# Sheet1.net
KiCad netlist of a schematic drawn in Altium Designer
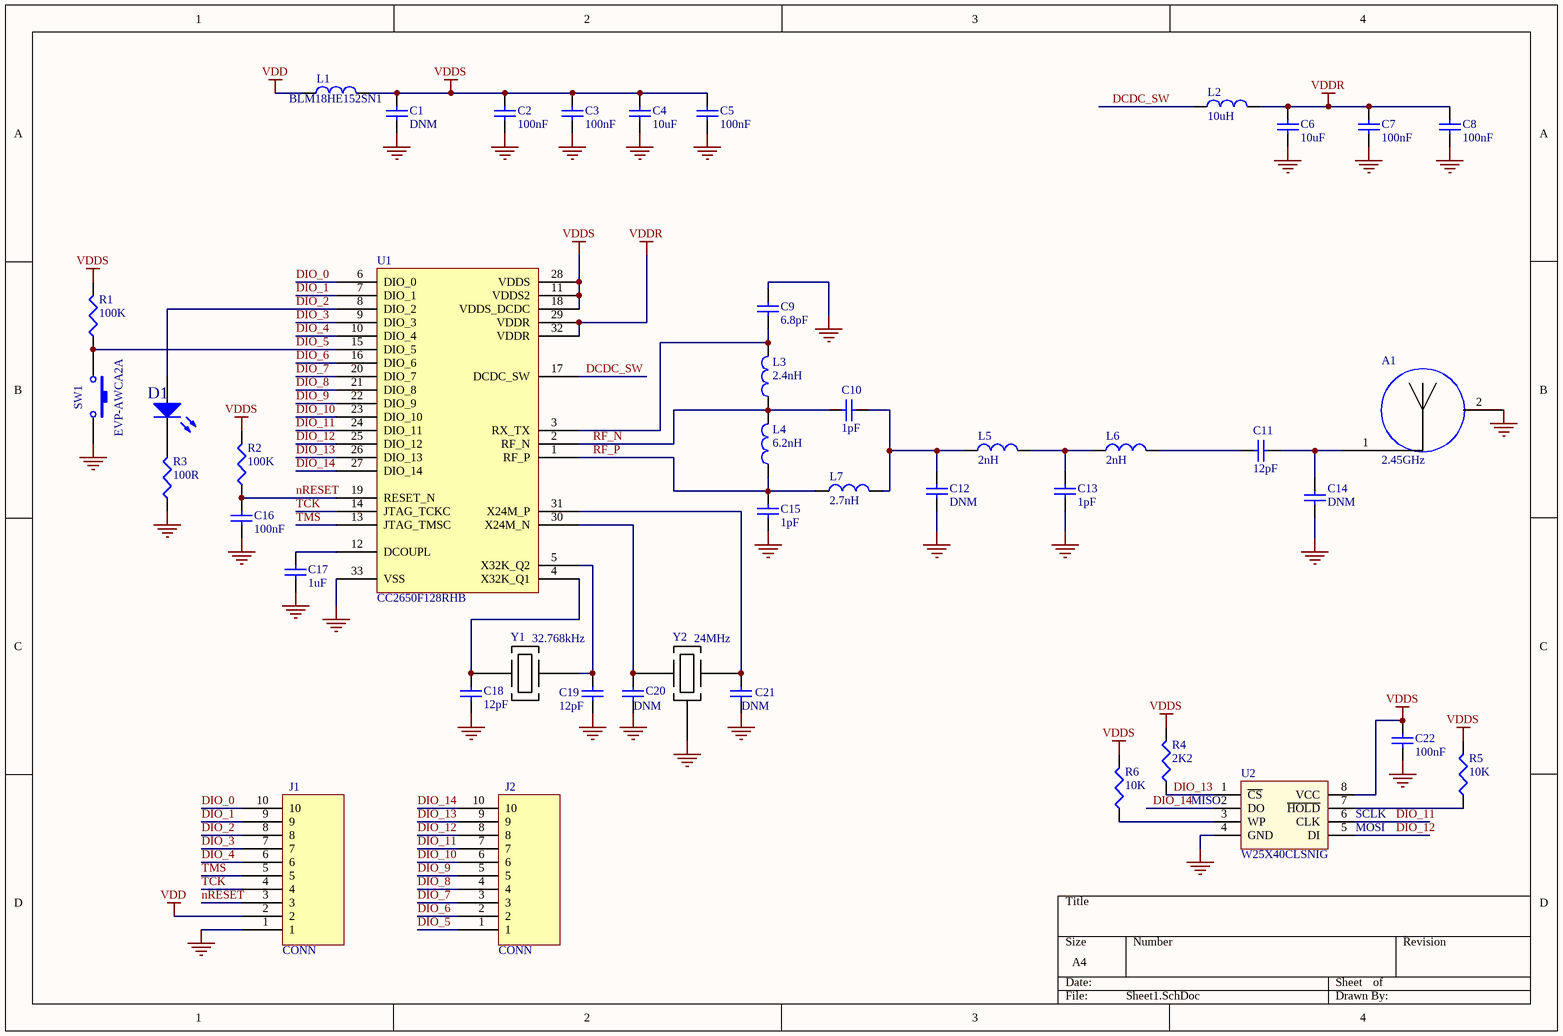
[diagram p0: Sheet1.SchDoc]

(export (version "E")
  (design (tool "Eeschema 10.0.6"))
  (components
    (comp (ref "A1")
      (value "2.45GHz")
      (footprint "ANTENNA_PCB_INATEL3")
      (description "ANTENNA 2.4GHz INATEL")
      (libsource (lib "Mechanical") (part "ANTENNA 2.4GHz_INATEL"))
    )
    (comp (ref "C1") (value "DNM") (footprint "0402") (libsource (lib "Schlib1") (part "CAP")))
    (comp (ref "C2")
      (value "100nF")
      (footprint "0402 - CAP")
      (description "CAP CER 0.1UF 6.3V 10% X7R 0402")
      (fields (field (name "MANUFACTURER") "Murata"))
      (libsource (lib "Schlib1") (part "CAP"))
    )
    (comp (ref "C3")
      (value "100nF")
      (footprint "0402 - CAP")
      (description "CAP CER 0.1UF 6.3V 10% X7R 0402")
      (fields (field (name "MANUFACTURER") "Murata"))
      (libsource (lib "Schlib1") (part "CAP"))
    )
    (comp (ref "C4")
      (value "10uF")
      (footprint "0603 - CAP")
      (description "CAP CER 10UF 6.3V 20% X5R 0603")
      (fields (field (name "MANUFACTURER") "Murata"))
      (libsource (lib "Schlib1") (part "CAP"))
    )
    (comp (ref "C5")
      (value "100nF")
      (footprint "0402 - CAP")
      (description "CAP CER 0.1UF 6.3V 10% X7R 0402")
      (fields (field (name "MANUFACTURER") "Murata"))
      (libsource (lib "Schlib1") (part "CAP"))
    )
    (comp (ref "C6")
      (value "10uF")
      (footprint "0603 - CAP")
      (description "CAP CER 10UF 6.3V 20% X5R 0603")
      (fields (field (name "MANUFACTURER") "Murata"))
      (libsource (lib "Schlib1") (part "CAP"))
    )
    (comp (ref "C7")
      (value "100nF")
      (footprint "0402 - CAP")
      (description "CAP CER 0.1UF 6.3V 10% X7R 0402")
      (fields (field (name "MANUFACTURER") "Murata"))
      (libsource (lib "Schlib1") (part "CAP"))
    )
    (comp (ref "C8")
      (value "100nF")
      (footprint "0402 - CAP")
      (description "CAP CER 0.1UF 6.3V 10% X7R 0402")
      (fields (field (name "MANUFACTURER") "Murata"))
      (libsource (lib "Schlib1") (part "CAP"))
    )
    (comp (ref "C9")
      (value "6.8pF")
      (footprint "0402 - CAP")
      (description "CAP CER 6.8PF 50V NP0 0402")
      (fields (field (name "MANUFACTURER") "Murata"))
      (libsource (lib "Schlib1") (part "CAP"))
    )
    (comp (ref "C10")
      (value "1pF")
      (footprint "0402 - CAP")
      (description "CAP CER 1PF 50V NP0 0402")
      (fields (field (name "MANUFACTURER") "Murata"))
      (libsource (lib "Schlib1") (part "CAP"))
    )
    (comp (ref "C11")
      (value "12pF")
      (footprint "0402 - CAP")
      (description "CAP CER 12PF 50V NP0 0402")
      (fields (field (name "MANUFACTURER") "Murata"))
      (libsource (lib "Schlib1") (part "CAP"))
    )
    (comp (ref "C12") (value "DNM") (footprint "0402") (libsource (lib "Schlib1") (part "CAP")))
    (comp (ref "C13")
      (value "1pF")
      (footprint "0402 - CAP")
      (description "CAP CER 1PF 50V NP0 0402")
      (fields (field (name "MANUFACTURER") "Murata"))
      (libsource (lib "Schlib1") (part "CAP"))
    )
    (comp (ref "C14") (value "DNM") (footprint "0402") (libsource (lib "Schlib1") (part "CAP")))
    (comp (ref "C15")
      (value "1pF")
      (footprint "0402 - CAP")
      (description "CAP CER 1PF 50V NP0 0402")
      (fields (field (name "MANUFACTURER") "Murata"))
      (libsource (lib "Schlib1") (part "CAP"))
    )
    (comp (ref "C16")
      (value "100nF")
      (footprint "0402 - CAP")
      (description "CAP CER 0.1UF 6.3V 10% X7R 0402")
      (fields (field (name "MANUFACTURER") "Murata"))
      (libsource (lib "Schlib1") (part "CAP"))
    )
    (comp (ref "C17")
      (value "1uF")
      (footprint "0402 - CAP")
      (description "CAP CER 1UF 10V 10% X5R 0402")
      (fields (field (name "MANUFACTURER") "Murata"))
      (libsource (lib "Schlib1") (part "CAP"))
    )
    (comp (ref "C18")
      (value "12pF")
      (footprint "0402 - CAP")
      (description "CAP CER 12PF 50V NP0 0402")
      (fields (field (name "MANUFACTURER") "Murata"))
      (libsource (lib "Schlib1") (part "CAP"))
    )
    (comp (ref "C19")
      (value "12pF")
      (footprint "0402 - CAP")
      (description "CAP CER 12PF 50V NP0 0402")
      (fields (field (name "MANUFACTURER") "Murata"))
      (libsource (lib "Schlib1") (part "CAP"))
    )
    (comp (ref "C20") (value "DNM") (footprint "0402") (libsource (lib "Schlib1") (part "CAP")))
    (comp (ref "C21") (value "DNM") (footprint "0402") (libsource (lib "Schlib1") (part "CAP")))
    (comp (ref "C22")
      (value "100nF")
      (footprint "0402 - CAP")
      (description "CAP CER 0.1UF 6.3V 10% X7R 0402")
      (fields (field (name "MANUFACTURER") "Murata"))
      (libsource (lib "Schlib1") (part "CAP"))
    )
    (comp (ref "D1")
      (value "Status")
      (footprint "0603 - LED")
      (description "LED SUPER RED CLR THIN 0603 SMD")
      (fields (field (name "MANUFACTURER") "Lite-On Inc"))
      (libsource (lib "Schlib1") (part "LED_R"))
    )
    (comp (ref "J1")
      (value "CONN")
      (footprint "CONN_HEADER ARDUINO SHIELD")
      (description "10POS SIL VERTICAL PIN HEADER")
      (fields (field (name "MANUFACTURER") "Harwin Inc"))
      (libsource (lib "Schlib1") (part "CONN"))
    )
    (comp (ref "J2")
      (value "CONN")
      (footprint "CONN_HEADER ARDUINO SHIELD")
      (description "10POS SIL VERTICAL PIN HEADER")
      (fields (field (name "MANUFACTURER") "Harwin Inc"))
      (libsource (lib "Schlib1") (part "CONN"))
    )
    (comp (ref "L1")
      (value "BLM18HE152SN1")
      (footprint "0603 - IND")
      (description "FERRITE CHIP 1500 OHM 500MA 0603")
      (fields (field (name "MANUFACTURER") "Murata"))
      (libsource (lib "") (part "INDUCTOR_1"))
    )
    (comp (ref "L2")
      (value "10uH")
      (footprint "0805 - CAP")
      (description "FIXED IND 10UH 110MA 520 MOHM")
      (fields (field (name "MANUFACTURER") "Taiyo Yuden"))
      (libsource (lib "") (part "INDUCTOR_1"))
    )
    (comp (ref "L3")
      (value "2.4nH")
      (footprint "0402 - IND")
      (description "FIXED IND 2.4NH 300MA 160 MOHM")
      (fields (field (name "MANUFACTURER") "Murata"))
      (libsource (lib "Schlib1") (part "INDUCTOR"))
    )
    (comp (ref "L4")
      (value "6.2nH")
      (footprint "0402 - IND")
      (description "FIXED IND 6.2NH 300MA 220 MOHM")
      (fields (field (name "MANUFACTURER") "Murata"))
      (libsource (lib "") (part "INDUCTOR_1"))
    )
    (comp (ref "L5")
      (value "2nH")
      (footprint "0402 - IND")
      (description "FIXED IND 2NH 300MA 100 MOHM SMD")
      (fields (field (name "MANUFACTURER") "Murata"))
      (libsource (lib "") (part "INDUCTOR_1"))
    )
    (comp (ref "L6")
      (value "2nH")
      (footprint "0402 - IND")
      (description "FIXED IND 2NH 300MA 100 MOHM SMD")
      (fields (field (name "MANUFACTURER") "Murata"))
      (libsource (lib "") (part "INDUCTOR_1"))
    )
    (comp (ref "L7")
      (value "2.7nH")
      (footprint "0402 - IND")
      (description "FIXED IND 2.7NH 300MA 150 MOHM")
      (fields (field (name "MANUFACTURER") "Murata"))
      (libsource (lib "") (part "INDUCTOR_1"))
    )
    (comp (ref "R1")
      (value "100K")
      (footprint "0402 - RES")
      (description "RES SMD 100K OHM 5% 1/10W 0402")
      (fields (field (name "MANUFACTURER") "Panasonic"))
      (libsource (lib "Schlib1") (part "RES"))
    )
    (comp (ref "R2")
      (value "100K")
      (footprint "0402 - RES")
      (description "RES SMD 100K OHM 5% 1/10W 0402")
      (fields (field (name "MANUFACTURER") "Panasonic"))
      (libsource (lib "Schlib1") (part "RES"))
    )
    (comp (ref "R3")
      (value "100R")
      (footprint "0402 - RES")
      (description "RES SMD 100 OHM 5% 1/10W 0402")
      (fields (field (name "MANUFACTURER") "Panasonic"))
      (libsource (lib "Schlib1") (part "RES"))
    )
    (comp (ref "R4")
      (value "2K2")
      (footprint "0402 - RES")
      (description "RES SMD 2.2K OHM 5% 1/10W 0402")
      (fields (field (name "MANUFACTURER") "Panasonic"))
      (libsource (lib "Schlib1") (part "RES"))
    )
    (comp (ref "R5")
      (value "10K")
      (footprint "0402 - RES")
      (description "RES SMD 10K OHM 5% 1/10W 0402")
      (fields (field (name "MANUFACTURER") "Panasonic"))
      (libsource (lib "Schlib1") (part "RES"))
    )
    (comp (ref "R6")
      (value "10K")
      (footprint "0402 - RES")
      (description "RES SMD 10K OHM 5% 1/10W 0402")
      (fields (field (name "MANUFACTURER") "Panasonic"))
      (libsource (lib "Schlib1") (part "RES"))
    )
    (comp (ref "SW1")
      (value "EVP-AWCA2A")
      (footprint "EVP-AWCA2A")
      (description "Tactile Switch SPST-NO Top Actuated Surface Mount")
      (fields (field (name "MANUFACTURER") "Panasonic"))
      (libsource (lib "Mechanical") (part "SW_EVPAW"))
    )
    (comp (ref "U1")
      (value "CC2650F128RHB")
      (footprint "CC2650F128RHB - cm")
      (description "IC MCU 128KB FLASH PHY 32VQFN")
      (fields (field (name "MANUFACTURER") "TI"))
      (libsource (lib "Schlib1") (part "CC2650F128RHB"))
    )
    (comp (ref "U2")
      (value "W25X40CLSNIG")
      (footprint "SOIC-8")
      (description "IC FLASH 4MBIT 104MHZ 8SOIC")
      (fields (field (name "MANUFACTURER") "Winbond"))
      (libsource (lib "Schlib1") (part "SPI_FLASH_SOIC_8"))
    )
    (comp (ref "Y1")
      (value "32.768kHz")
      (footprint "FC-12M")
      (description "Crystal 32.7680kHz 20ppm 12.5pF 90 kOhm -40°C - 85°C Surface Mount 2-SMD")
      (fields (field (name "MANUFACTURER") "EPSON"))
      (libsource (lib "") (part "XTAL1_1"))
    )
    (comp (ref "Y2")
      (value "24MHz")
      (footprint "XT_DFN_LCC_32x25")
      (description "Crystal 24.0000MHz 10ppm 9pF 40 Ohm -40°C - 85°C Surface Mount 4-SMD, No Lead (DFN, LCC)")
      (fields (field (name "MANUFACTURER") "EPSON"))
      (libsource (lib "Schlib1") (part "XTAL1"))
    )
  )
  (nets
    (net (code "1") (name "/DCDC_SW") (class "Default")
      (node (ref "L2") (pin "2") (pinfunction "2_2") (pintype "passive"))
      (node (ref "U1") (pin "17") (pinfunction "DCDC_SW_17") (pintype "passive"))
    )
    (net (code "2") (name "/DIO_0") (class "Default")
      (node (ref "J2") (pin "10") (pinfunction "10_10") (pintype "passive"))
      (node (ref "U1") (pin "6") (pinfunction "DIO_0_6") (pintype "passive"))
    )
    (net (code "3") (name "/DIO_1") (class "Default")
      (node (ref "J2") (pin "9") (pinfunction "9_9") (pintype "passive"))
      (node (ref "U1") (pin "7") (pinfunction "DIO_1_7") (pintype "passive"))
    )
    (net (code "4") (name "/DIO_2") (class "Default")
      (node (ref "D1") (pin "1") (pinfunction "A_1") (pintype "passive"))
      (node (ref "J2") (pin "8") (pinfunction "8_8") (pintype "passive"))
      (node (ref "U1") (pin "8") (pinfunction "DIO_2_8") (pintype "passive"))
    )
    (net (code "5") (name "/DIO_3") (class "Default")
      (node (ref "J2") (pin "7") (pinfunction "7_7") (pintype "passive"))
      (node (ref "U1") (pin "9") (pinfunction "DIO_3_9") (pintype "passive"))
    )
    (net (code "6") (name "/DIO_4") (class "Default")
      (node (ref "J2") (pin "6") (pinfunction "6_6") (pintype "passive"))
      (node (ref "U1") (pin "10") (pinfunction "DIO_4_10") (pintype "passive"))
    )
    (net (code "7") (name "/DIO_5") (class "Default")
      (node (ref "J1") (pin "1") (pinfunction "1_1") (pintype "passive"))
      (node (ref "R1") (pin "1") (pinfunction "1_1") (pintype "passive"))
      (node (ref "SW1") (pin "1") (pinfunction "1_1") (pintype "passive"))
      (node (ref "U1") (pin "15") (pinfunction "DIO_5_15") (pintype "passive"))
    )
    (net (code "8") (name "/DIO_6") (class "Default")
      (node (ref "J1") (pin "2") (pinfunction "2_2") (pintype "passive"))
      (node (ref "U1") (pin "16") (pinfunction "DIO_6_16") (pintype "passive"))
    )
    (net (code "9") (name "/DIO_7") (class "Default")
      (node (ref "J1") (pin "3") (pinfunction "3_3") (pintype "passive"))
      (node (ref "U1") (pin "20") (pinfunction "DIO_7_20") (pintype "passive"))
    )
    (net (code "10") (name "/DIO_8") (class "Default")
      (node (ref "J1") (pin "4") (pinfunction "4_4") (pintype "passive"))
      (node (ref "U1") (pin "21") (pinfunction "DIO_8_21") (pintype "passive"))
    )
    (net (code "11") (name "/DIO_9") (class "Default")
      (node (ref "J1") (pin "5") (pinfunction "5_5") (pintype "passive"))
      (node (ref "U1") (pin "22") (pinfunction "DIO_9_22") (pintype "passive"))
    )
    (net (code "12") (name "/DIO_10") (class "Default")
      (node (ref "J1") (pin "6") (pinfunction "6_6") (pintype "passive"))
      (node (ref "U1") (pin "23") (pinfunction "DIO_10_23") (pintype "passive"))
    )
    (net (code "13") (name "/DIO_11") (class "Default")
      (node (ref "J1") (pin "7") (pinfunction "7_7") (pintype "passive"))
      (node (ref "U1") (pin "24") (pinfunction "DIO_11_24") (pintype "passive"))
      (node (ref "U2") (pin "6") (pinfunction "CLK_6") (pintype "passive"))
    )
    (net (code "14") (name "/DIO_12") (class "Default")
      (node (ref "J1") (pin "8") (pinfunction "8_8") (pintype "passive"))
      (node (ref "U1") (pin "25") (pinfunction "DIO_12_25") (pintype "passive"))
      (node (ref "U2") (pin "5") (pinfunction "DI_5") (pintype "passive"))
    )
    (net (code "15") (name "/DIO_13") (class "Default")
      (node (ref "J1") (pin "9") (pinfunction "9_9") (pintype "passive"))
      (node (ref "R4") (pin "1") (pinfunction "1_1") (pintype "passive"))
      (node (ref "U1") (pin "26") (pinfunction "DIO_13_26") (pintype "passive"))
      (node (ref "U2") (pin "1") (pinfunction "~{CS}_1") (pintype "passive"))
    )
    (net (code "16") (name "/DIO_14") (class "Default")
      (node (ref "J1") (pin "10") (pinfunction "10_10") (pintype "passive"))
      (node (ref "U1") (pin "27") (pinfunction "DIO_14_27") (pintype "passive"))
      (node (ref "U2") (pin "2") (pinfunction "DO_2") (pintype "passive"))
    )
    (net (code "17") (name "/RF_N") (class "Default")
      (node (ref "C10") (pin "2") (pinfunction "2_2") (pintype "passive"))
      (node (ref "L3") (pin "1") (pinfunction "1_1") (pintype "passive"))
      (node (ref "L4") (pin "1") (pinfunction "1_1") (pintype "passive"))
      (node (ref "U1") (pin "2") (pinfunction "RF_N_2") (pintype "passive"))
    )
    (net (code "18") (name "/RF_P") (class "Default")
      (node (ref "C15") (pin "1") (pinfunction "1_1") (pintype "passive"))
      (node (ref "L4") (pin "2") (pinfunction "2_2") (pintype "passive"))
      (node (ref "L7") (pin "2") (pinfunction "2_2") (pintype "passive"))
      (node (ref "U1") (pin "1") (pinfunction "RF_P_1") (pintype "passive"))
    )
    (net (code "19") (name "/TCK") (class "Default")
      (node (ref "J2") (pin "4") (pinfunction "4_4") (pintype "passive"))
      (node (ref "U1") (pin "14") (pinfunction "JTAG_TCKC_14") (pintype "passive"))
    )
    (net (code "20") (name "/TMS") (class "Default")
      (node (ref "J2") (pin "5") (pinfunction "5_5") (pintype "passive"))
      (node (ref "U1") (pin "13") (pinfunction "JTAG_TMSC_13") (pintype "passive"))
    )
    (net (code "21") (name "/nRESET") (class "Default")
      (node (ref "C16") (pin "2") (pinfunction "2_2") (pintype "passive"))
      (node (ref "J2") (pin "3") (pinfunction "3_3") (pintype "passive"))
      (node (ref "R2") (pin "1") (pinfunction "1_1") (pintype "passive"))
      (node (ref "U1") (pin "19") (pinfunction "RESET_N_19") (pintype "passive"))
    )
    (net (code "22") (name "GND") (class "Default")
      (node (ref "A1") (pin "2") (pinfunction "2_2") (pintype "passive"))
      (node (ref "C1") (pin "1") (pinfunction "1_1") (pintype "passive"))
      (node (ref "C12") (pin "1") (pinfunction "1_1") (pintype "passive"))
      (node (ref "C13") (pin "1") (pinfunction "1_1") (pintype "passive"))
      (node (ref "C14") (pin "1") (pinfunction "1_1") (pintype "passive"))
      (node (ref "C15") (pin "2") (pinfunction "2_2") (pintype "passive"))
      (node (ref "C16") (pin "1") (pinfunction "1_1") (pintype "passive"))
      (node (ref "C17") (pin "1") (pinfunction "1_1") (pintype "passive"))
      (node (ref "C18") (pin "1") (pinfunction "1_1") (pintype "passive"))
      (node (ref "C19") (pin "1") (pinfunction "1_1") (pintype "passive"))
      (node (ref "C2") (pin "1") (pinfunction "1_1") (pintype "passive"))
      (node (ref "C20") (pin "1") (pinfunction "1_1") (pintype "passive"))
      (node (ref "C21") (pin "1") (pinfunction "1_1") (pintype "passive"))
      (node (ref "C22") (pin "1") (pinfunction "1_1") (pintype "passive"))
      (node (ref "C3") (pin "1") (pinfunction "1_1") (pintype "passive"))
      (node (ref "C4") (pin "1") (pinfunction "1_1") (pintype "passive"))
      (node (ref "C5") (pin "1") (pinfunction "1_1") (pintype "passive"))
      (node (ref "C6") (pin "1") (pinfunction "1_1") (pintype "passive"))
      (node (ref "C7") (pin "1") (pinfunction "1_1") (pintype "passive"))
      (node (ref "C8") (pin "1") (pinfunction "1_1") (pintype "passive"))
      (node (ref "C9") (pin "2") (pinfunction "2_2") (pintype "passive"))
      (node (ref "J2") (pin "1") (pinfunction "1_1") (pintype "passive"))
      (node (ref "R3") (pin "1") (pinfunction "1_1") (pintype "passive"))
      (node (ref "SW1") (pin "2") (pinfunction "2_2") (pintype "passive"))
      (node (ref "U1") (pin "33") (pinfunction "VSS_33") (pintype "passive"))
      (node (ref "U2") (pin "4") (pinfunction "GND_4") (pintype "passive"))
      (node (ref "Y2") (pin "3") (pinfunction "3_3") (pintype "passive"))
    )
    (net (code "23") (name "Net-(A1-Pad1)") (class "Default")
      (node (ref "A1") (pin "1") (pinfunction "1_1") (pintype "passive"))
      (node (ref "C11") (pin "1") (pinfunction "1_1") (pintype "passive"))
      (node (ref "C14") (pin "2") (pinfunction "2_2") (pintype "passive"))
    )
    (net (code "24") (name "Net-(C10-Pad1)") (class "Default")
      (node (ref "C10") (pin "1") (pinfunction "1_1") (pintype "passive"))
      (node (ref "C12") (pin "2") (pinfunction "2_2") (pintype "passive"))
      (node (ref "L5") (pin "2") (pinfunction "2_2") (pintype "passive"))
      (node (ref "L7") (pin "1") (pinfunction "1_1") (pintype "passive"))
    )
    (net (code "25") (name "Net-(C11-Pad2)") (class "Default")
      (node (ref "C11") (pin "2") (pinfunction "2_2") (pintype "passive"))
      (node (ref "L6") (pin "1") (pinfunction "1_1") (pintype "passive"))
    )
    (net (code "26") (name "Net-(C13-Pad2)") (class "Default")
      (node (ref "C13") (pin "2") (pinfunction "2_2") (pintype "passive"))
      (node (ref "L5") (pin "1") (pinfunction "1_1") (pintype "passive"))
      (node (ref "L6") (pin "2") (pinfunction "2_2") (pintype "passive"))
    )
    (net (code "27") (name "Net-(D1-K)") (class "Default")
      (node (ref "D1") (pin "2") (pinfunction "K_2") (pintype "passive"))
      (node (ref "R3") (pin "2") (pinfunction "2_2") (pintype "passive"))
    )
    (net (code "28") (name "Net-(U1-DCOUPL)") (class "Default")
      (node (ref "C17") (pin "2") (pinfunction "2_2") (pintype "passive"))
      (node (ref "U1") (pin "12") (pinfunction "DCOUPL_12") (pintype "passive"))
    )
    (net (code "29") (name "Net-(U1-RX_TX)") (class "Default")
      (node (ref "C9") (pin "1") (pinfunction "1_1") (pintype "passive"))
      (node (ref "L3") (pin "2") (pinfunction "2_2") (pintype "passive"))
      (node (ref "U1") (pin "3") (pinfunction "RX_TX_3") (pintype "passive"))
    )
    (net (code "30") (name "Net-(U1-X24M_N)") (class "Default")
      (node (ref "C20") (pin "2") (pinfunction "2_2") (pintype "passive"))
      (node (ref "U1") (pin "30") (pinfunction "X24M_N_30") (pintype "passive"))
      (node (ref "Y2") (pin "1") (pinfunction "1_1") (pintype "passive"))
    )
    (net (code "31") (name "Net-(U1-X24M_P)") (class "Default")
      (node (ref "C21") (pin "2") (pinfunction "2_2") (pintype "passive"))
      (node (ref "U1") (pin "31") (pinfunction "X24M_P_31") (pintype "passive"))
      (node (ref "Y2") (pin "2") (pinfunction "2_2") (pintype "passive"))
    )
    (net (code "32") (name "Net-(U1-X32K_Q1)") (class "Default")
      (node (ref "C18") (pin "2") (pinfunction "2_2") (pintype "passive"))
      (node (ref "U1") (pin "4") (pinfunction "X32K_Q1_4") (pintype "passive"))
      (node (ref "Y1") (pin "1") (pinfunction "1_1") (pintype "passive"))
    )
    (net (code "33") (name "Net-(U1-X32K_Q2)") (class "Default")
      (node (ref "C19") (pin "2") (pinfunction "2_2") (pintype "passive"))
      (node (ref "U1") (pin "5") (pinfunction "X32K_Q2_5") (pintype "passive"))
      (node (ref "Y1") (pin "2") (pinfunction "2_2") (pintype "passive"))
    )
    (net (code "34") (name "Net-(U2-WP)") (class "Default")
      (node (ref "R6") (pin "1") (pinfunction "1_1") (pintype "passive"))
      (node (ref "U2") (pin "3") (pinfunction "WP_3") (pintype "passive"))
    )
    (net (code "35") (name "Net-(U2-~{HOLD})") (class "Default")
      (node (ref "R5") (pin "1") (pinfunction "1_1") (pintype "passive"))
      (node (ref "U2") (pin "7") (pinfunction "~{HOLD}_7") (pintype "passive"))
    )
    (net (code "36") (name "VDD") (class "Default")
      (node (ref "J2") (pin "2") (pinfunction "2_2") (pintype "passive"))
      (node (ref "L1") (pin "2") (pinfunction "2_2") (pintype "passive"))
    )
    (net (code "37") (name "VDDR") (class "Default")
      (node (ref "C6") (pin "2") (pinfunction "2_2") (pintype "passive"))
      (node (ref "C7") (pin "2") (pinfunction "2_2") (pintype "passive"))
      (node (ref "C8") (pin "2") (pinfunction "2_2") (pintype "passive"))
      (node (ref "L2") (pin "1") (pinfunction "1_1") (pintype "passive"))
      (node (ref "U1") (pin "29") (pinfunction "VDDR_29") (pintype "passive"))
      (node (ref "U1") (pin "32") (pinfunction "VDDR_32") (pintype "passive"))
    )
    (net (code "38") (name "VDDS") (class "Default")
      (node (ref "C1") (pin "2") (pinfunction "2_2") (pintype "passive"))
      (node (ref "C2") (pin "2") (pinfunction "2_2") (pintype "passive"))
      (node (ref "C22") (pin "2") (pinfunction "2_2") (pintype "passive"))
      (node (ref "C3") (pin "2") (pinfunction "2_2") (pintype "passive"))
      (node (ref "C4") (pin "2") (pinfunction "2_2") (pintype "passive"))
      (node (ref "C5") (pin "2") (pinfunction "2_2") (pintype "passive"))
      (node (ref "L1") (pin "1") (pinfunction "1_1") (pintype "passive"))
      (node (ref "R1") (pin "2") (pinfunction "2_2") (pintype "passive"))
      (node (ref "R2") (pin "2") (pinfunction "2_2") (pintype "passive"))
      (node (ref "R4") (pin "2") (pinfunction "2_2") (pintype "passive"))
      (node (ref "R5") (pin "2") (pinfunction "2_2") (pintype "passive"))
      (node (ref "R6") (pin "2") (pinfunction "2_2") (pintype "passive"))
      (node (ref "U1") (pin "11") (pinfunction "VDDS2_11") (pintype "passive"))
      (node (ref "U1") (pin "18") (pinfunction "VDDS_DCDC_18") (pintype "passive"))
      (node (ref "U1") (pin "28") (pinfunction "VDDS_28") (pintype "passive"))
      (node (ref "U2") (pin "8") (pinfunction "VCC_8") (pintype "passive"))
    )
    (net (code "39") (name "unconnected-(Y1-Pad3)") (class "Default")
      (node (ref "Y1") (pin "3") (pinfunction "3_3") (pintype "passive"))
    )
  )
)
